# rs485_board.net
KiCad netlist of a schematic drawn in EAGLE
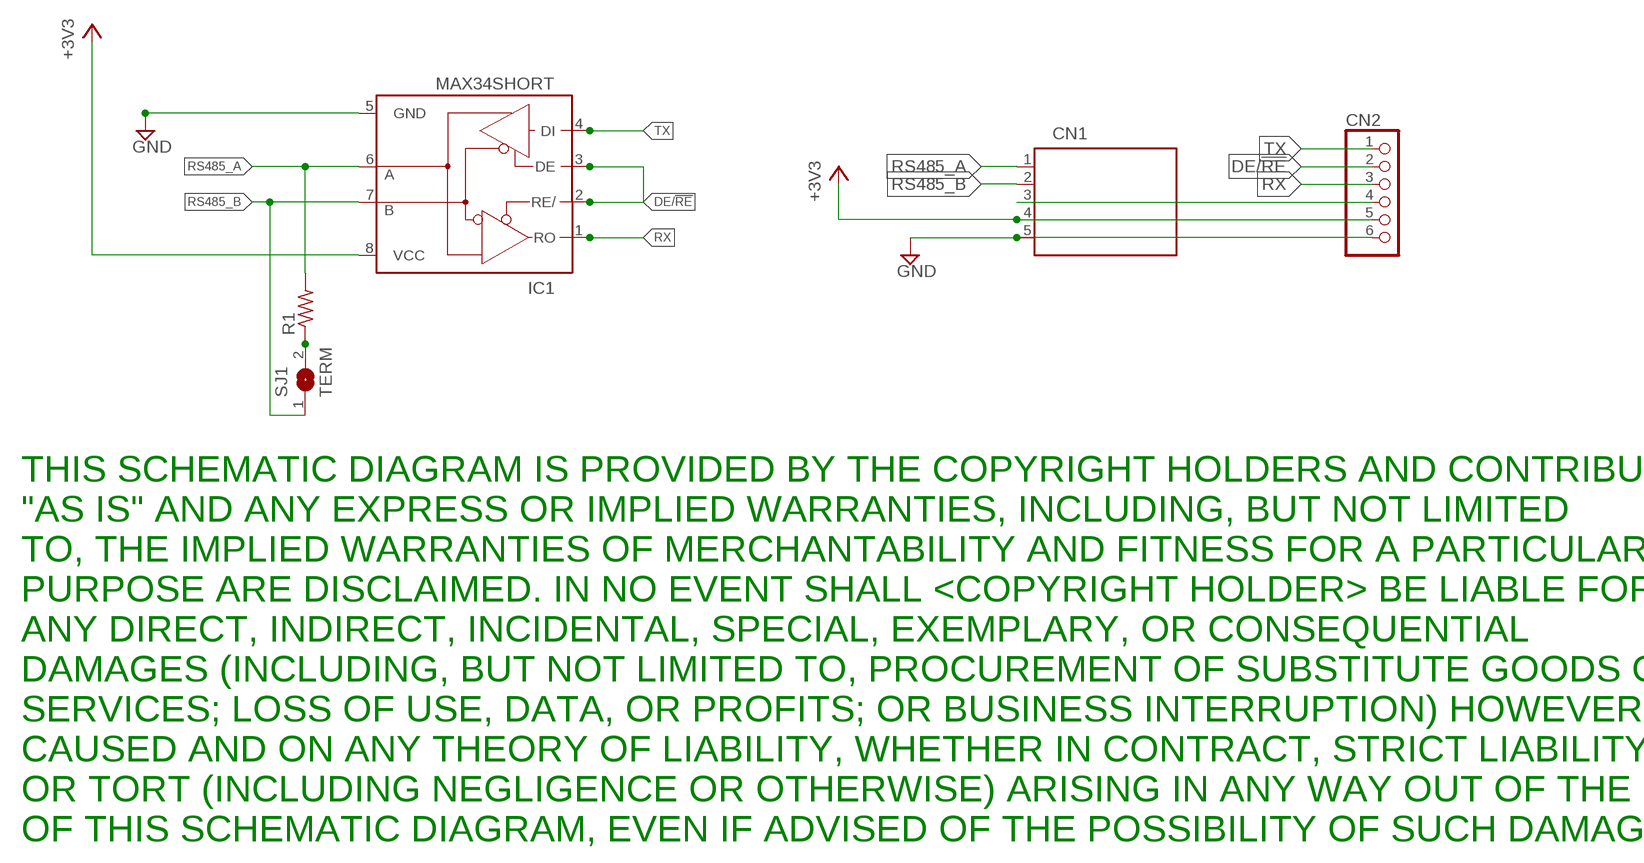
[diagram p0: schematic, sheet 1]

(export (version "E")
  (design (tool "Eeschema 10.0.6"))
  (components
    (comp (ref "CN1")
      (value "5PINZH")
      (footprint "eagle-import:ZH-5")
      (libsource (lib "eagle-import") (part "5PINZH"))
    )
    (comp (ref "CN2")
      (value "PINHD-1X06_2.54")
      (footprint "eagle-import:1X06")
      (libsource (lib "eagle-import") (part "PINHD-1X06_2.54"))
    )
    (comp (ref "IC1")
      (value "MAX34SHORT")
      (footprint "eagle-import:SO08SHORT")
      (libsource (lib "eagle-import") (part "MAX34SHORT"))
    )
    (comp (ref "R1")
      (value "R-US_R0603")
      (footprint "eagle-import:R0603")
      (libsource (lib "eagle-import") (part "R-US_R0603"))
    )
    (comp (ref "SJ1")
      (value "TERM")
      (footprint "eagle-import:SJ")
      (libsource (lib "eagle-import") (part "SJ"))
    )
  )
  (nets
    (net (code "1") (name "+3V3") (class "Default")
      (node (ref "CN1") (pin "4") (pinfunction "4_4") (pintype "passive"))
      (node (ref "CN2") (pin "5") (pinfunction "5_5") (pintype "passive"))
      (node (ref "IC1") (pin "8") (pinfunction "VCC_8") (pintype "power_in"))
    )
    (net (code "2") (name "/DE{slash}~{RE}") (class "Default")
      (node (ref "CN2") (pin "2") (pinfunction "2_2") (pintype "passive"))
      (node (ref "IC1") (pin "2") (pinfunction "RE/_2") (pintype "input"))
      (node (ref "IC1") (pin "3") (pinfunction "DE_3") (pintype "input"))
    )
    (net (code "3") (name "GND") (class "Default")
      (node (ref "CN1") (pin "5") (pinfunction "5_5") (pintype "passive"))
      (node (ref "CN2") (pin "6") (pinfunction "6_6") (pintype "passive"))
      (node (ref "IC1") (pin "5") (pinfunction "GND_5") (pintype "power_in"))
    )
    (net (code "4") (name "Net-(CN1-Pad3)") (class "Default")
      (node (ref "CN1") (pin "3") (pinfunction "3_3") (pintype "passive"))
      (node (ref "CN2") (pin "4") (pinfunction "4_4") (pintype "passive"))
    )
    (net (code "5") (name "Net-(R1-Pad1)") (class "Default")
      (node (ref "R1") (pin "1") (pinfunction "1_1") (pintype "passive"))
      (node (ref "SJ1") (pin "2") (pinfunction "2_2") (pintype "passive"))
    )
    (net (code "6") (name "RS485_A") (class "Default")
      (node (ref "CN1") (pin "1") (pinfunction "1_1") (pintype "passive"))
      (node (ref "IC1") (pin "6") (pinfunction "A_6") (pintype "passive"))
      (node (ref "R1") (pin "2") (pinfunction "2_2") (pintype "passive"))
    )
    (net (code "7") (name "RS485_B") (class "Default")
      (node (ref "CN1") (pin "2") (pinfunction "2_2") (pintype "passive"))
      (node (ref "IC1") (pin "7") (pinfunction "B_7") (pintype "passive"))
      (node (ref "SJ1") (pin "1") (pinfunction "1_1") (pintype "passive"))
    )
    (net (code "8") (name "RX") (class "Default")
      (node (ref "CN2") (pin "3") (pinfunction "3_3") (pintype "passive"))
      (node (ref "IC1") (pin "1") (pinfunction "RO_1") (pintype "output"))
    )
    (net (code "9") (name "TX") (class "Default")
      (node (ref "CN2") (pin "1") (pinfunction "1_1") (pintype "passive"))
      (node (ref "IC1") (pin "4") (pinfunction "DI_4") (pintype "input"))
    )
  )
)
